# a320-polyvoks-vcf.net
KiCad netlist of a schematic drawn in EAGLE
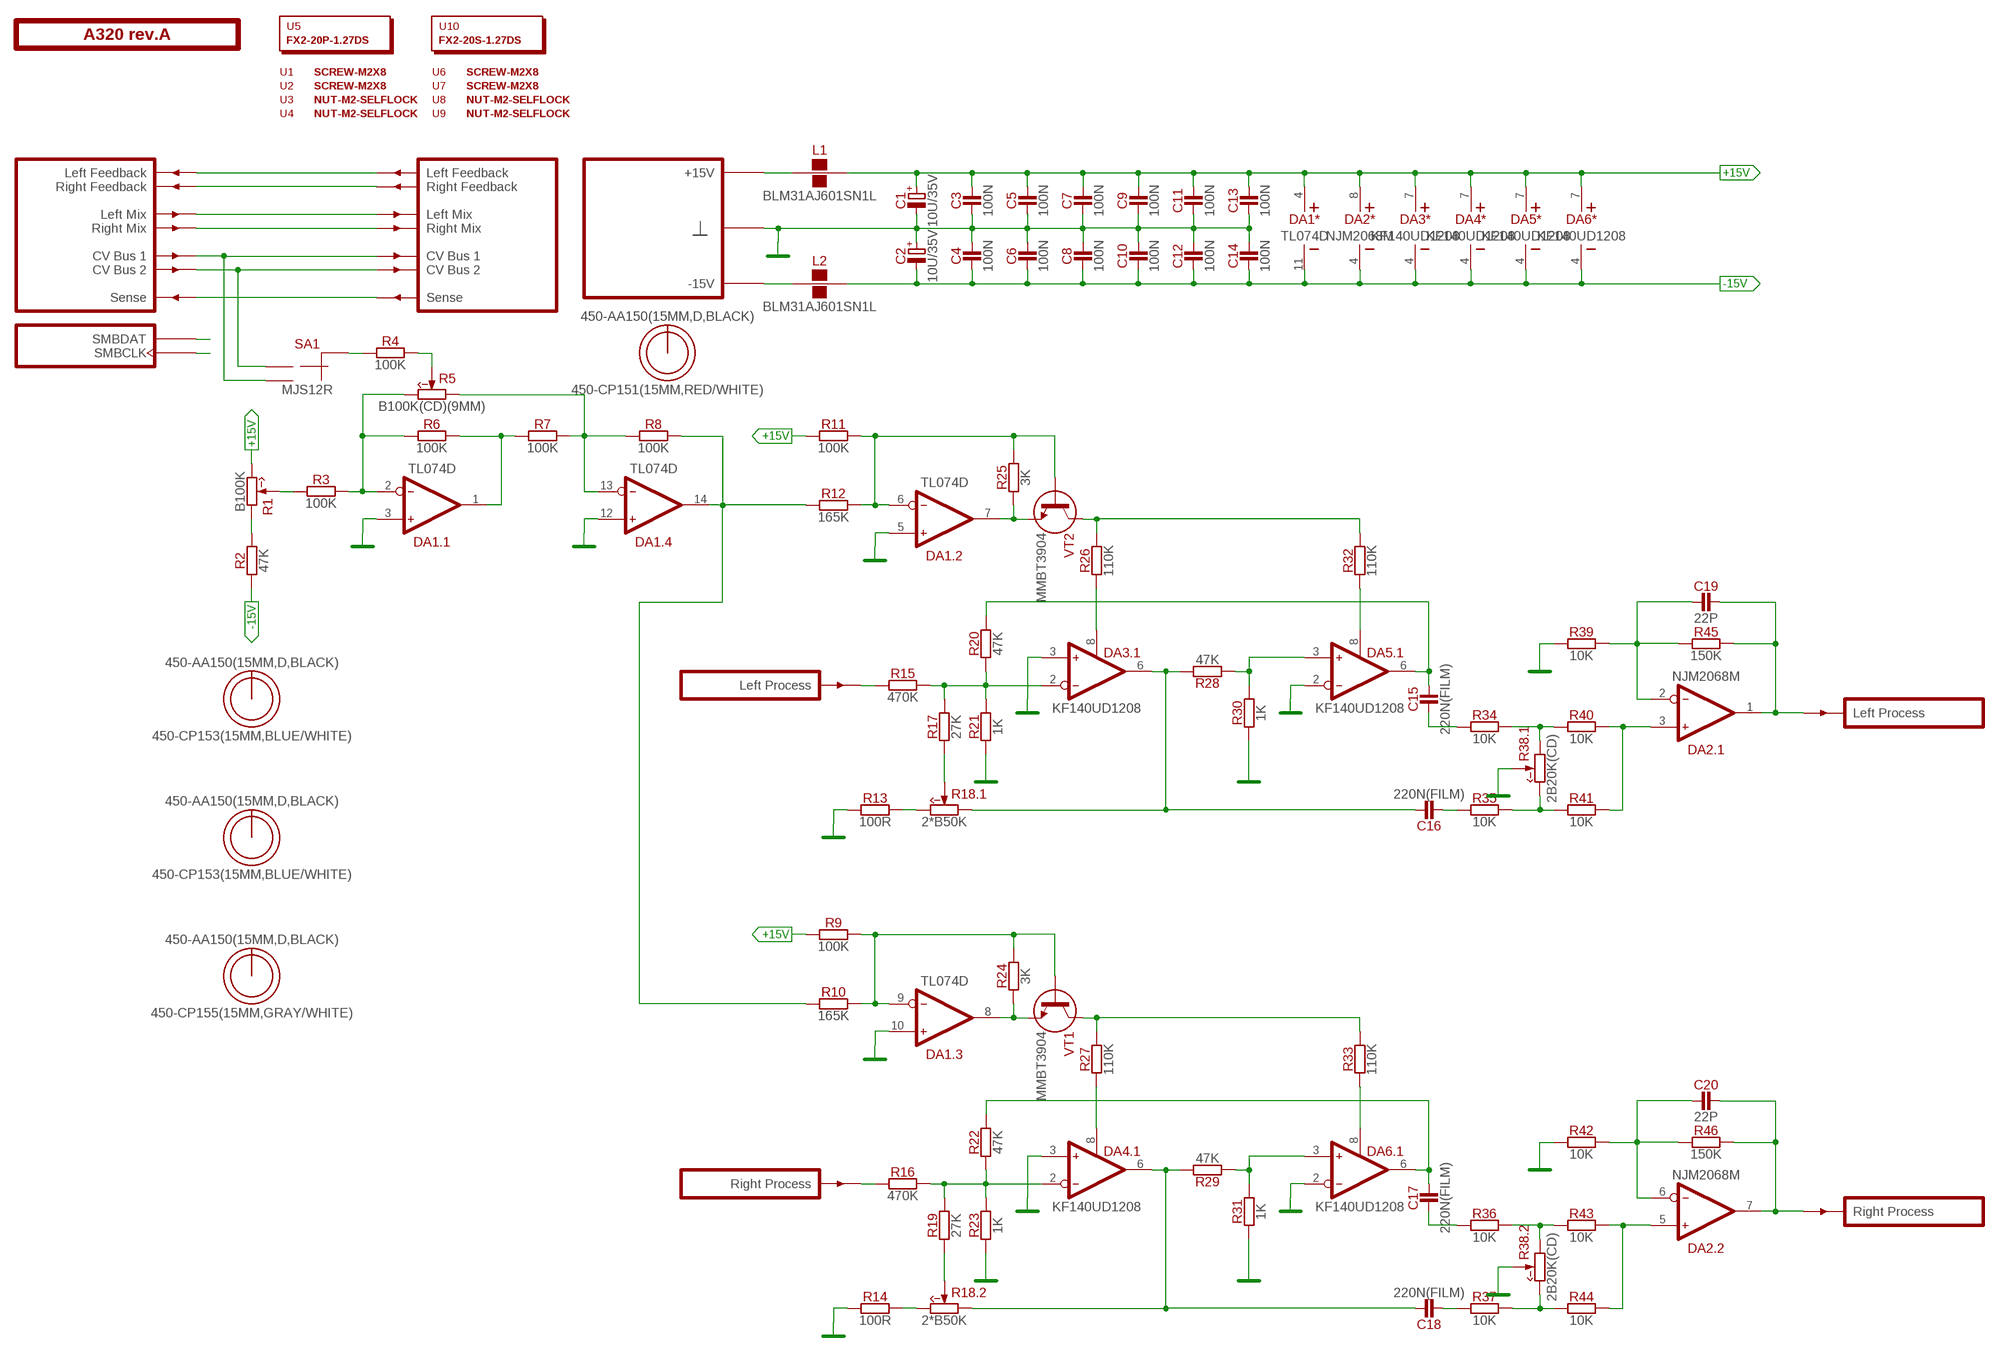
[diagram p0: schematic, sheet 1]

(export (version "E")
  (design (tool "Eeschema 10.0.6"))
  (components
    (comp (ref "C1")
      (value "10U/35V")
      (footprint "eagle-import:E2-5")
      (libsource (lib "eagle-import") (part "?10U/35V"))
    )
    (comp (ref "C2")
      (value "10U/35V")
      (footprint "eagle-import:E2-5")
      (libsource (lib "eagle-import") (part "?10U/35V"))
    )
    (comp (ref "C3")
      (value "100N")
      (footprint "eagle-import:C-0805")
      (libsource (lib "eagle-import") (part "?100N"))
    )
    (comp (ref "C4")
      (value "100N")
      (footprint "eagle-import:C-0805")
      (libsource (lib "eagle-import") (part "?100N"))
    )
    (comp (ref "C5")
      (value "100N")
      (footprint "eagle-import:C-0805")
      (libsource (lib "eagle-import") (part "?100N"))
    )
    (comp (ref "C6")
      (value "100N")
      (footprint "eagle-import:C-0805")
      (libsource (lib "eagle-import") (part "?100N"))
    )
    (comp (ref "C7")
      (value "100N")
      (footprint "eagle-import:C-0805")
      (libsource (lib "eagle-import") (part "?100N"))
    )
    (comp (ref "C8")
      (value "100N")
      (footprint "eagle-import:C-0805")
      (libsource (lib "eagle-import") (part "?100N"))
    )
    (comp (ref "C9")
      (value "100N")
      (footprint "eagle-import:C-0805")
      (libsource (lib "eagle-import") (part "?100N"))
    )
    (comp (ref "C10")
      (value "100N")
      (footprint "eagle-import:C-0805")
      (libsource (lib "eagle-import") (part "?100N"))
    )
    (comp (ref "C11")
      (value "100N")
      (footprint "eagle-import:C-0805")
      (libsource (lib "eagle-import") (part "?100N"))
    )
    (comp (ref "C12")
      (value "100N")
      (footprint "eagle-import:C-0805")
      (libsource (lib "eagle-import") (part "?100N"))
    )
    (comp (ref "C13")
      (value "100N")
      (footprint "eagle-import:C-0805")
      (libsource (lib "eagle-import") (part "?100N"))
    )
    (comp (ref "C14")
      (value "100N")
      (footprint "eagle-import:C-0805")
      (libsource (lib "eagle-import") (part "?100N"))
    )
    (comp (ref "C15")
      (value "220N(FILM)")
      (footprint "eagle-import:C050-025X075")
      (libsource (lib "eagle-import") (part "?220N(FILM)"))
    )
    (comp (ref "C16")
      (value "220N(FILM)")
      (footprint "eagle-import:C050-025X075")
      (libsource (lib "eagle-import") (part "?220N(FILM)"))
    )
    (comp (ref "C17")
      (value "220N(FILM)")
      (footprint "eagle-import:C050-025X075")
      (libsource (lib "eagle-import") (part "?220N(FILM)"))
    )
    (comp (ref "C18")
      (value "220N(FILM)")
      (footprint "eagle-import:C050-025X075")
      (libsource (lib "eagle-import") (part "?220N(FILM)"))
    )
    (comp (ref "C19")
      (value "22P")
      (footprint "eagle-import:C-0805")
      (libsource (lib "eagle-import") (part "?22P"))
    )
    (comp (ref "C20")
      (value "22P")
      (footprint "eagle-import:C-0805")
      (libsource (lib "eagle-import") (part "?22P"))
    )
    (comp (ref "DA1")
      (value "TL074D")
      (footprint "eagle-import:SO-14")
      (libsource (lib "eagle-import") (part "TL074D"))
    )
    (comp (ref "DA2")
      (value "NJM2068M")
      (footprint "eagle-import:SO-8")
      (libsource (lib "eagle-import") (part "NJM2068M"))
    )
    (comp (ref "DA3")
      (value "KF140UD1208")
      (footprint "eagle-import:SO-8")
      (libsource (lib "eagle-import") (part "KF140UD1208"))
    )
    (comp (ref "DA4")
      (value "KF140UD1208")
      (footprint "eagle-import:SO-8")
      (libsource (lib "eagle-import") (part "KF140UD1208"))
    )
    (comp (ref "DA5")
      (value "KF140UD1208")
      (footprint "eagle-import:SO-8")
      (libsource (lib "eagle-import") (part "KF140UD1208"))
    )
    (comp (ref "DA6")
      (value "KF140UD1208")
      (footprint "eagle-import:SO-8")
      (libsource (lib "eagle-import") (part "KF140UD1208"))
    )
    (comp (ref "L1")
      (value "BLM31AJ601SN1L")
      (footprint "eagle-import:1206")
      (libsource (lib "eagle-import") (part "BLM31AJ601SN1L"))
    )
    (comp (ref "L2")
      (value "BLM31AJ601SN1L")
      (footprint "eagle-import:1206")
      (libsource (lib "eagle-import") (part "BLM31AJ601SN1L"))
    )
    (comp (ref "O1")
      (value "450-AA150(15MM,D,BLACK)")
      (footprint "eagle-import:EMPTY")
      (libsource (lib "eagle-import") (part "450-AA?150(15MM,D,BLACK)"))
    )
    (comp (ref "O2")
      (value "450-CP153(15MM,BLUE/WHITE)")
      (footprint "eagle-import:EMPTY")
      (libsource (lib "eagle-import") (part "450-C?P153(15MM,BLUE/WHITE)"))
    )
    (comp (ref "O3")
      (value "450-AA150(15MM,D,BLACK)")
      (footprint "eagle-import:EMPTY")
      (libsource (lib "eagle-import") (part "450-AA?150(15MM,D,BLACK)"))
    )
    (comp (ref "O4")
      (value "450-CP153(15MM,BLUE/WHITE)")
      (footprint "eagle-import:EMPTY")
      (libsource (lib "eagle-import") (part "450-C?P153(15MM,BLUE/WHITE)"))
    )
    (comp (ref "O5")
      (value "450-AA150(15MM,D,BLACK)")
      (footprint "eagle-import:EMPTY")
      (libsource (lib "eagle-import") (part "450-AA?150(15MM,D,BLACK)"))
    )
    (comp (ref "O6")
      (value "450-CP155(15MM,GRAY/WHITE)")
      (footprint "eagle-import:EMPTY")
      (libsource (lib "eagle-import") (part "450-C?P155(15MM,GRAY/WHITE)"))
    )
    (comp (ref "O7")
      (value "450-AA150(15MM,D,BLACK)")
      (footprint "eagle-import:EMPTY")
      (libsource (lib "eagle-import") (part "450-AA?150(15MM,D,BLACK)"))
    )
    (comp (ref "O8")
      (value "450-CP151(15MM,RED/WHITE)")
      (footprint "eagle-import:EMPTY")
      (libsource (lib "eagle-import") (part "450-C?P151(15MM,RED/WHITE)"))
    )
    (comp (ref "PCB1")
      (value "A320 rev.A")
      (footprint "eagle-import:ST2-BOARD-50")
      (libsource (lib "eagle-import") (part "ST2-BOARD-?50"))
    )
    (comp (ref "R1")
      (value "B100K")
      (footprint "eagle-import:RV11-SINGLE")
      (libsource (lib "eagle-import") (part "?B100K"))
    )
    (comp (ref "R2")
      (value "47K")
      (footprint "eagle-import:R-0805")
      (libsource (lib "eagle-import") (part "?47K"))
    )
    (comp (ref "R3")
      (value "100K")
      (footprint "eagle-import:R-0805")
      (libsource (lib "eagle-import") (part "?100K"))
    )
    (comp (ref "R4")
      (value "100K")
      (footprint "eagle-import:R-0805")
      (libsource (lib "eagle-import") (part "?100K"))
    )
    (comp (ref "R5")
      (value "B100K(CD)(9MM)")
      (footprint "eagle-import:RV09-SINGLE")
      (libsource (lib "eagle-import") (part "?B100K(CD)(9MM)"))
    )
    (comp (ref "R6")
      (value "100K")
      (footprint "eagle-import:R-0805")
      (libsource (lib "eagle-import") (part "?100K"))
    )
    (comp (ref "R7")
      (value "100K")
      (footprint "eagle-import:R-0805")
      (libsource (lib "eagle-import") (part "?100K"))
    )
    (comp (ref "R8")
      (value "100K")
      (footprint "eagle-import:R-0805")
      (libsource (lib "eagle-import") (part "?100K"))
    )
    (comp (ref "R9")
      (value "100K")
      (footprint "eagle-import:R-0805")
      (libsource (lib "eagle-import") (part "?100K"))
    )
    (comp (ref "R10")
      (value "165K")
      (footprint "eagle-import:R-0805")
      (libsource (lib "eagle-import") (part "?165K"))
    )
    (comp (ref "R11")
      (value "100K")
      (footprint "eagle-import:R-0805")
      (libsource (lib "eagle-import") (part "?100K"))
    )
    (comp (ref "R12")
      (value "165K")
      (footprint "eagle-import:R-0805")
      (libsource (lib "eagle-import") (part "?165K"))
    )
    (comp (ref "R13")
      (value "100R")
      (footprint "eagle-import:R-0805")
      (libsource (lib "eagle-import") (part "?100R"))
    )
    (comp (ref "R14")
      (value "100R")
      (footprint "eagle-import:R-0805")
      (libsource (lib "eagle-import") (part "?100R"))
    )
    (comp (ref "R15")
      (value "470K")
      (footprint "eagle-import:R-0805")
      (libsource (lib "eagle-import") (part "?470K"))
    )
    (comp (ref "R16")
      (value "470K")
      (footprint "eagle-import:R-0805")
      (libsource (lib "eagle-import") (part "?470K"))
    )
    (comp (ref "R17")
      (value "27K")
      (footprint "eagle-import:R-0805")
      (libsource (lib "eagle-import") (part "?27K"))
    )
    (comp (ref "R18")
      (value "2*B50K")
      (footprint "eagle-import:RV11-DUAL")
      (libsource (lib "eagle-import") (part "potentiometers_2?B50K"))
    )
    (comp (ref "R19")
      (value "27K")
      (footprint "eagle-import:R-0805")
      (libsource (lib "eagle-import") (part "?27K"))
    )
    (comp (ref "R20")
      (value "47K")
      (footprint "eagle-import:R-0805")
      (libsource (lib "eagle-import") (part "?47K"))
    )
    (comp (ref "R21")
      (value "1K")
      (footprint "eagle-import:R-0805")
      (libsource (lib "eagle-import") (part "?1K"))
    )
    (comp (ref "R22")
      (value "47K")
      (footprint "eagle-import:R-0805")
      (libsource (lib "eagle-import") (part "?47K"))
    )
    (comp (ref "R23")
      (value "1K")
      (footprint "eagle-import:R-0805")
      (libsource (lib "eagle-import") (part "?1K"))
    )
    (comp (ref "R24")
      (value "3K")
      (footprint "eagle-import:R-0805")
      (libsource (lib "eagle-import") (part "?3K"))
    )
    (comp (ref "R25")
      (value "3K")
      (footprint "eagle-import:R-0805")
      (libsource (lib "eagle-import") (part "?3K"))
    )
    (comp (ref "R26")
      (value "110K")
      (footprint "eagle-import:R-0805")
      (libsource (lib "eagle-import") (part "?110K"))
    )
    (comp (ref "R27")
      (value "110K")
      (footprint "eagle-import:R-0805")
      (libsource (lib "eagle-import") (part "?110K"))
    )
    (comp (ref "R28")
      (value "47K")
      (footprint "eagle-import:R-0805")
      (libsource (lib "eagle-import") (part "?47K"))
    )
    (comp (ref "R29")
      (value "47K")
      (footprint "eagle-import:R-0805")
      (libsource (lib "eagle-import") (part "?47K"))
    )
    (comp (ref "R30")
      (value "1K")
      (footprint "eagle-import:R-0805")
      (libsource (lib "eagle-import") (part "?1K"))
    )
    (comp (ref "R31")
      (value "1K")
      (footprint "eagle-import:R-0805")
      (libsource (lib "eagle-import") (part "?1K"))
    )
    (comp (ref "R32")
      (value "110K")
      (footprint "eagle-import:R-0805")
      (libsource (lib "eagle-import") (part "?110K"))
    )
    (comp (ref "R33")
      (value "110K")
      (footprint "eagle-import:R-0805")
      (libsource (lib "eagle-import") (part "?110K"))
    )
    (comp (ref "R34")
      (value "10K")
      (footprint "eagle-import:R-0805")
      (libsource (lib "eagle-import") (part "?10K"))
    )
    (comp (ref "R35")
      (value "10K")
      (footprint "eagle-import:R-0805")
      (libsource (lib "eagle-import") (part "?10K"))
    )
    (comp (ref "R36")
      (value "10K")
      (footprint "eagle-import:R-0805")
      (libsource (lib "eagle-import") (part "?10K"))
    )
    (comp (ref "R37")
      (value "10K")
      (footprint "eagle-import:R-0805")
      (libsource (lib "eagle-import") (part "?10K"))
    )
    (comp (ref "R38")
      (value "2B20K(CD)")
      (footprint "eagle-import:RV11-DUAL")
      (libsource (lib "eagle-import") (part "2?B20K(CD)"))
    )
    (comp (ref "R39")
      (value "10K")
      (footprint "eagle-import:R-0805")
      (libsource (lib "eagle-import") (part "?10K"))
    )
    (comp (ref "R40")
      (value "10K")
      (footprint "eagle-import:R-0805")
      (libsource (lib "eagle-import") (part "?10K"))
    )
    (comp (ref "R41")
      (value "10K")
      (footprint "eagle-import:R-0805")
      (libsource (lib "eagle-import") (part "?10K"))
    )
    (comp (ref "R42")
      (value "10K")
      (footprint "eagle-import:R-0805")
      (libsource (lib "eagle-import") (part "?10K"))
    )
    (comp (ref "R43")
      (value "10K")
      (footprint "eagle-import:R-0805")
      (libsource (lib "eagle-import") (part "?10K"))
    )
    (comp (ref "R44")
      (value "10K")
      (footprint "eagle-import:R-0805")
      (libsource (lib "eagle-import") (part "?10K"))
    )
    (comp (ref "R45")
      (value "150K")
      (footprint "eagle-import:R-0805")
      (libsource (lib "eagle-import") (part "?150K"))
    )
    (comp (ref "R46")
      (value "150K")
      (footprint "eagle-import:R-0805")
      (libsource (lib "eagle-import") (part "?150K"))
    )
    (comp (ref "SA1")
      (value "MJS12R")
      (footprint "eagle-import:APEM-MJS12R")
      (libsource (lib "eagle-import") (part "MJS12R"))
    )
    (comp (ref "U1")
      (value "SCREW-M2X8")
      (footprint "eagle-import:EMPTY")
      (libsource (lib "eagle-import") (part "?SCREW-M2X8"))
    )
    (comp (ref "U2")
      (value "SCREW-M2X8")
      (footprint "eagle-import:EMPTY")
      (libsource (lib "eagle-import") (part "?SCREW-M2X8"))
    )
    (comp (ref "U3")
      (value "NUT-M2-SELFLOCK")
      (footprint "eagle-import:EMPTY")
      (libsource (lib "eagle-import") (part "?NUT-M2-SELFLOCK"))
    )
    (comp (ref "U4")
      (value "NUT-M2-SELFLOCK")
      (footprint "eagle-import:EMPTY")
      (libsource (lib "eagle-import") (part "?NUT-M2-SELFLOCK"))
    )
    (comp (ref "U5")
      (value "FX2-20P-1.27DS")
      (footprint "eagle-import:EMPTY")
      (libsource (lib "eagle-import") (part "?FX2-20P-1.27DS"))
    )
    (comp (ref "U6")
      (value "SCREW-M2X8")
      (footprint "eagle-import:EMPTY")
      (libsource (lib "eagle-import") (part "?SCREW-M2X8"))
    )
    (comp (ref "U7")
      (value "SCREW-M2X8")
      (footprint "eagle-import:EMPTY")
      (libsource (lib "eagle-import") (part "?SCREW-M2X8"))
    )
    (comp (ref "U8")
      (value "NUT-M2-SELFLOCK")
      (footprint "eagle-import:EMPTY")
      (libsource (lib "eagle-import") (part "?NUT-M2-SELFLOCK"))
    )
    (comp (ref "U9")
      (value "NUT-M2-SELFLOCK")
      (footprint "eagle-import:EMPTY")
      (libsource (lib "eagle-import") (part "?NUT-M2-SELFLOCK"))
    )
    (comp (ref "U10")
      (value "FX2-20S-1.27DS")
      (footprint "eagle-import:EMPTY")
      (libsource (lib "eagle-import") (part "?FX2-20S-1.27DS"))
    )
    (comp (ref "VT1")
      (value "MMBT3904")
      (footprint "eagle-import:SOT23")
      (libsource (lib "eagle-import") (part "?MMBT3904"))
    )
    (comp (ref "VT2")
      (value "MMBT3904")
      (footprint "eagle-import:SOT23")
      (libsource (lib "eagle-import") (part "?MMBT3904"))
    )
  )
  (nets
    (net (code "1") (name "+15V") (class "Default")
      (node (ref "C1") (pin "+") (pinfunction "+_+") (pintype "passive"))
      (node (ref "C11") (pin "2") (pinfunction "2_2") (pintype "passive"))
      (node (ref "C13") (pin "2") (pinfunction "2_2") (pintype "passive"))
      (node (ref "C3") (pin "2") (pinfunction "2_2") (pintype "passive"))
      (node (ref "C5") (pin "2") (pinfunction "2_2") (pintype "passive"))
      (node (ref "C7") (pin "2") (pinfunction "2_2") (pintype "passive"))
      (node (ref "C9") (pin "2") (pinfunction "2_2") (pintype "passive"))
      (node (ref "DA1") (pin "4") (pinfunction "V+_4") (pintype "power_in"))
      (node (ref "DA2") (pin "8") (pinfunction "V+_8") (pintype "power_in"))
      (node (ref "DA3") (pin "7") (pinfunction "V+_7") (pintype "power_in"))
      (node (ref "DA4") (pin "7") (pinfunction "V+_7") (pintype "power_in"))
      (node (ref "DA5") (pin "7") (pinfunction "V+_7") (pintype "power_in"))
      (node (ref "DA6") (pin "7") (pinfunction "V+_7") (pintype "power_in"))
      (node (ref "L1") (pin "2") (pinfunction "2_2") (pintype "passive"))
      (node (ref "R1") (pin "3") (pinfunction "CW_3") (pintype "passive"))
      (node (ref "R11") (pin "1") (pinfunction "1_1") (pintype "passive"))
      (node (ref "R9") (pin "1") (pinfunction "1_1") (pintype "passive"))
    )
    (net (code "2") (name "-15V") (class "Default")
      (node (ref "C10") (pin "1") (pinfunction "1_1") (pintype "passive"))
      (node (ref "C12") (pin "1") (pinfunction "1_1") (pintype "passive"))
      (node (ref "C14") (pin "1") (pinfunction "1_1") (pintype "passive"))
      (node (ref "C2") (pin "-") (pinfunction "-_-") (pintype "passive"))
      (node (ref "C4") (pin "1") (pinfunction "1_1") (pintype "passive"))
      (node (ref "C6") (pin "1") (pinfunction "1_1") (pintype "passive"))
      (node (ref "C8") (pin "1") (pinfunction "1_1") (pintype "passive"))
      (node (ref "DA1") (pin "11") (pinfunction "V-_11") (pintype "power_in"))
      (node (ref "DA2") (pin "4") (pinfunction "V-_4") (pintype "power_in"))
      (node (ref "DA3") (pin "4") (pinfunction "V-_4") (pintype "power_in"))
      (node (ref "DA4") (pin "4") (pinfunction "V-_4") (pintype "power_in"))
      (node (ref "DA5") (pin "4") (pinfunction "V-_4") (pintype "power_in"))
      (node (ref "DA6") (pin "4") (pinfunction "V-_4") (pintype "power_in"))
      (node (ref "L2") (pin "2") (pinfunction "2_2") (pintype "passive"))
      (node (ref "R2") (pin "1") (pinfunction "1_1") (pintype "passive"))
    )
    (net (code "3") (name "GND") (class "Default")
      (node (ref "C1") (pin "-") (pinfunction "-_-") (pintype "passive"))
      (node (ref "C10") (pin "2") (pinfunction "2_2") (pintype "passive"))
      (node (ref "C11") (pin "1") (pinfunction "1_1") (pintype "passive"))
      (node (ref "C12") (pin "2") (pinfunction "2_2") (pintype "passive"))
      (node (ref "C13") (pin "1") (pinfunction "1_1") (pintype "passive"))
      (node (ref "C14") (pin "2") (pinfunction "2_2") (pintype "passive"))
      (node (ref "C2") (pin "+") (pinfunction "+_+") (pintype "passive"))
      (node (ref "C3") (pin "1") (pinfunction "1_1") (pintype "passive"))
      (node (ref "C4") (pin "2") (pinfunction "2_2") (pintype "passive"))
      (node (ref "C5") (pin "1") (pinfunction "1_1") (pintype "passive"))
      (node (ref "C6") (pin "2") (pinfunction "2_2") (pintype "passive"))
      (node (ref "C7") (pin "1") (pinfunction "1_1") (pintype "passive"))
      (node (ref "C8") (pin "2") (pinfunction "2_2") (pintype "passive"))
      (node (ref "C9") (pin "1") (pinfunction "1_1") (pintype "passive"))
      (node (ref "DA1") (pin "10") (pinfunction "IN+_10") (pintype "input"))
      (node (ref "DA1") (pin "12") (pinfunction "IN+_12") (pintype "input"))
      (node (ref "DA1") (pin "3") (pinfunction "IN+_3") (pintype "input"))
      (node (ref "DA1") (pin "5") (pinfunction "IN+_5") (pintype "input"))
      (node (ref "DA3") (pin "3") (pinfunction "IN+_3") (pintype "input"))
      (node (ref "DA4") (pin "3") (pinfunction "IN+_3") (pintype "input"))
      (node (ref "DA5") (pin "2") (pinfunction "IN-_2") (pintype "input"))
      (node (ref "DA6") (pin "2") (pinfunction "IN-_2") (pintype "input"))
      (node (ref "PCB1") (pin "B4") (pinfunction "GND_B4") (pintype "bidirectional"))
      (node (ref "PCB1") (pin "B4'") (pinfunction "GND_B4'") (pintype "bidirectional"))
      (node (ref "PCB1") (pin "B5") (pinfunction "GND_B5") (pintype "bidirectional"))
      (node (ref "PCB1") (pin "B5'") (pinfunction "GND_B5'") (pintype "bidirectional"))
      (node (ref "PCB1") (pin "B6") (pinfunction "GND_B6") (pintype "bidirectional"))
      (node (ref "PCB1") (pin "B6'") (pinfunction "GND_B6'") (pintype "bidirectional"))
      (node (ref "PCB1") (pin "B7") (pinfunction "GND_B7") (pintype "bidirectional"))
      (node (ref "PCB1") (pin "B7'") (pinfunction "GND_B7'") (pintype "bidirectional"))
      (node (ref "PCB1") (pin "B8") (pinfunction "GND_B8") (pintype "bidirectional"))
      (node (ref "PCB1") (pin "B8'") (pinfunction "GND_B8'") (pintype "bidirectional"))
      (node (ref "R13") (pin "1") (pinfunction "1_1") (pintype "passive"))
      (node (ref "R14") (pin "1") (pinfunction "1_1") (pintype "passive"))
      (node (ref "R21") (pin "1") (pinfunction "1_1") (pintype "passive"))
      (node (ref "R23") (pin "1") (pinfunction "1_1") (pintype "passive"))
      (node (ref "R30") (pin "1") (pinfunction "1_1") (pintype "passive"))
      (node (ref "R31") (pin "1") (pinfunction "1_1") (pintype "passive"))
      (node (ref "R38") (pin "2") (pinfunction "W_2") (pintype "passive"))
      (node (ref "R38") (pin "2'") (pinfunction "W_2'") (pintype "passive"))
      (node (ref "R39") (pin "1") (pinfunction "1_1") (pintype "passive"))
      (node (ref "R42") (pin "1") (pinfunction "1_1") (pintype "passive"))
    )
    (net (code "4") (name "Net-(C15-Pad1)") (class "Default")
      (node (ref "C15") (pin "1") (pinfunction "1_1") (pintype "passive"))
      (node (ref "R34") (pin "1") (pinfunction "1_1") (pintype "passive"))
    )
    (net (code "5") (name "Net-(C16-Pad1)") (class "Default")
      (node (ref "C16") (pin "1") (pinfunction "1_1") (pintype "passive"))
      (node (ref "R35") (pin "1") (pinfunction "1_1") (pintype "passive"))
    )
    (net (code "6") (name "Net-(C17-Pad1)") (class "Default")
      (node (ref "C17") (pin "1") (pinfunction "1_1") (pintype "passive"))
      (node (ref "R36") (pin "1") (pinfunction "1_1") (pintype "passive"))
    )
    (net (code "7") (name "Net-(C18-Pad1)") (class "Default")
      (node (ref "C18") (pin "1") (pinfunction "1_1") (pintype "passive"))
      (node (ref "R37") (pin "1") (pinfunction "1_1") (pintype "passive"))
    )
    (net (code "8") (name "Net-(DA1B-IN-)") (class "Default")
      (node (ref "DA1") (pin "2") (pinfunction "IN-_2") (pintype "input"))
      (node (ref "R3") (pin "2") (pinfunction "2_2") (pintype "passive"))
      (node (ref "R5") (pin "3") (pinfunction "CW_3") (pintype "passive"))
      (node (ref "R6") (pin "1") (pinfunction "1_1") (pintype "passive"))
    )
    (net (code "9") (name "Net-(DA1B-OUT)") (class "Default")
      (node (ref "DA1") (pin "1") (pinfunction "OUT_1") (pintype "output"))
      (node (ref "R6") (pin "2") (pinfunction "2_2") (pintype "passive"))
      (node (ref "R7") (pin "1") (pinfunction "1_1") (pintype "passive"))
    )
    (net (code "10") (name "Net-(DA1C-IN-)") (class "Default")
      (node (ref "DA1") (pin "6") (pinfunction "IN-_6") (pintype "input"))
      (node (ref "R11") (pin "2") (pinfunction "2_2") (pintype "passive"))
      (node (ref "R12") (pin "2") (pinfunction "2_2") (pintype "passive"))
      (node (ref "R25") (pin "2") (pinfunction "2_2") (pintype "passive"))
      (node (ref "VT2") (pin "1") (pinfunction "B_1") (pintype "passive"))
    )
    (net (code "11") (name "Net-(DA1C-OUT)") (class "Default")
      (node (ref "DA1") (pin "7") (pinfunction "OUT_7") (pintype "output"))
      (node (ref "R25") (pin "1") (pinfunction "1_1") (pintype "passive"))
      (node (ref "VT2") (pin "2") (pinfunction "E_2") (pintype "passive"))
    )
    (net (code "12") (name "Net-(DA1D-IN-)") (class "Default")
      (node (ref "DA1") (pin "9") (pinfunction "IN-_9") (pintype "input"))
      (node (ref "R10") (pin "2") (pinfunction "2_2") (pintype "passive"))
      (node (ref "R24") (pin "2") (pinfunction "2_2") (pintype "passive"))
      (node (ref "R9") (pin "2") (pinfunction "2_2") (pintype "passive"))
      (node (ref "VT1") (pin "1") (pinfunction "B_1") (pintype "passive"))
    )
    (net (code "13") (name "Net-(DA1D-OUT)") (class "Default")
      (node (ref "DA1") (pin "8") (pinfunction "OUT_8") (pintype "output"))
      (node (ref "R24") (pin "1") (pinfunction "1_1") (pintype "passive"))
      (node (ref "VT1") (pin "2") (pinfunction "E_2") (pintype "passive"))
    )
    (net (code "14") (name "Net-(DA1E-IN-)") (class "Default")
      (node (ref "DA1") (pin "13") (pinfunction "IN-_13") (pintype "input"))
      (node (ref "R5") (pin "1") (pinfunction "CCW_1") (pintype "passive"))
      (node (ref "R7") (pin "2") (pinfunction "2_2") (pintype "passive"))
      (node (ref "R8") (pin "1") (pinfunction "1_1") (pintype "passive"))
    )
    (net (code "15") (name "Net-(DA1E-OUT)") (class "Default")
      (node (ref "DA1") (pin "14") (pinfunction "OUT_14") (pintype "output"))
      (node (ref "R10") (pin "1") (pinfunction "1_1") (pintype "passive"))
      (node (ref "R12") (pin "1") (pinfunction "1_1") (pintype "passive"))
      (node (ref "R8") (pin "2") (pinfunction "2_2") (pintype "passive"))
    )
    (net (code "16") (name "Net-(DA2B-IN+)") (class "Default")
      (node (ref "DA2") (pin "3") (pinfunction "IN+_3") (pintype "input"))
      (node (ref "R40") (pin "2") (pinfunction "2_2") (pintype "passive"))
      (node (ref "R41") (pin "2") (pinfunction "2_2") (pintype "passive"))
    )
    (net (code "17") (name "Net-(DA2B-IN-)") (class "Default")
      (node (ref "C19") (pin "1") (pinfunction "1_1") (pintype "passive"))
      (node (ref "DA2") (pin "2") (pinfunction "IN-_2") (pintype "input"))
      (node (ref "R39") (pin "2") (pinfunction "2_2") (pintype "passive"))
      (node (ref "R45") (pin "1") (pinfunction "1_1") (pintype "passive"))
    )
    (net (code "18") (name "Net-(DA2B-OUT)") (class "Default")
      (node (ref "C19") (pin "2") (pinfunction "2_2") (pintype "passive"))
      (node (ref "DA2") (pin "1") (pinfunction "OUT_1") (pintype "output"))
      (node (ref "PCB1") (pin "BOUTL'") (pinfunction "OUTL_BOUTL'") (pintype "bidirectional"))
      (node (ref "R45") (pin "2") (pinfunction "2_2") (pintype "passive"))
    )
    (net (code "19") (name "Net-(DA2C-IN+)") (class "Default")
      (node (ref "DA2") (pin "5") (pinfunction "IN+_5") (pintype "input"))
      (node (ref "R43") (pin "2") (pinfunction "2_2") (pintype "passive"))
      (node (ref "R44") (pin "2") (pinfunction "2_2") (pintype "passive"))
    )
    (net (code "20") (name "Net-(DA2C-IN-)") (class "Default")
      (node (ref "C20") (pin "1") (pinfunction "1_1") (pintype "passive"))
      (node (ref "DA2") (pin "6") (pinfunction "IN-_6") (pintype "input"))
      (node (ref "R42") (pin "2") (pinfunction "2_2") (pintype "passive"))
      (node (ref "R46") (pin "1") (pinfunction "1_1") (pintype "passive"))
    )
    (net (code "21") (name "Net-(DA2C-OUT)") (class "Default")
      (node (ref "C20") (pin "2") (pinfunction "2_2") (pintype "passive"))
      (node (ref "DA2") (pin "7") (pinfunction "OUT_7") (pintype "output"))
      (node (ref "PCB1") (pin "BOUTR'") (pinfunction "OUTR_BOUTR'") (pintype "bidirectional"))
      (node (ref "R46") (pin "2") (pinfunction "2_2") (pintype "passive"))
    )
    (net (code "22") (name "Net-(DA3B-IN-)") (class "Default")
      (node (ref "DA3") (pin "2") (pinfunction "IN-_2") (pintype "input"))
      (node (ref "R15") (pin "2") (pinfunction "2_2") (pintype "passive"))
      (node (ref "R17") (pin "2") (pinfunction "2_2") (pintype "passive"))
      (node (ref "R20") (pin "1") (pinfunction "1_1") (pintype "passive"))
      (node (ref "R21") (pin "2") (pinfunction "2_2") (pintype "passive"))
    )
    (net (code "23") (name "Net-(DA3B-ISET)") (class "Default")
      (node (ref "DA3") (pin "8") (pinfunction "ISET_8") (pintype "bidirectional"))
      (node (ref "R26") (pin "1") (pinfunction "1_1") (pintype "passive"))
    )
    (net (code "24") (name "Net-(DA3B-OUT)") (class "Default")
      (node (ref "C16") (pin "2") (pinfunction "2_2") (pintype "passive"))
      (node (ref "DA3") (pin "6") (pinfunction "OUT_6") (pintype "output"))
      (node (ref "R18") (pin "1") (pinfunction "CCW_1") (pintype "passive"))
      (node (ref "R28") (pin "2") (pinfunction "2_2") (pintype "passive"))
    )
    (net (code "25") (name "Net-(DA4B-IN-)") (class "Default")
      (node (ref "DA4") (pin "2") (pinfunction "IN-_2") (pintype "input"))
      (node (ref "R16") (pin "2") (pinfunction "2_2") (pintype "passive"))
      (node (ref "R19") (pin "2") (pinfunction "2_2") (pintype "passive"))
      (node (ref "R22") (pin "1") (pinfunction "1_1") (pintype "passive"))
      (node (ref "R23") (pin "2") (pinfunction "2_2") (pintype "passive"))
    )
    (net (code "26") (name "Net-(DA4B-ISET)") (class "Default")
      (node (ref "DA4") (pin "8") (pinfunction "ISET_8") (pintype "bidirectional"))
      (node (ref "R27") (pin "1") (pinfunction "1_1") (pintype "passive"))
    )
    (net (code "27") (name "Net-(DA4B-OUT)") (class "Default")
      (node (ref "C18") (pin "2") (pinfunction "2_2") (pintype "passive"))
      (node (ref "DA4") (pin "6") (pinfunction "OUT_6") (pintype "output"))
      (node (ref "R18") (pin "1'") (pinfunction "CCW_1'") (pintype "passive"))
      (node (ref "R29") (pin "2") (pinfunction "2_2") (pintype "passive"))
    )
    (net (code "28") (name "Net-(DA5B-IN+)") (class "Default")
      (node (ref "DA5") (pin "3") (pinfunction "IN+_3") (pintype "input"))
      (node (ref "R28") (pin "1") (pinfunction "1_1") (pintype "passive"))
      (node (ref "R30") (pin "2") (pinfunction "2_2") (pintype "passive"))
    )
    (net (code "29") (name "Net-(DA5B-ISET)") (class "Default")
      (node (ref "DA5") (pin "8") (pinfunction "ISET_8") (pintype "bidirectional"))
      (node (ref "R32") (pin "1") (pinfunction "1_1") (pintype "passive"))
    )
    (net (code "30") (name "Net-(DA5B-OUT)") (class "Default")
      (node (ref "C15") (pin "2") (pinfunction "2_2") (pintype "passive"))
      (node (ref "DA5") (pin "6") (pinfunction "OUT_6") (pintype "output"))
      (node (ref "R20") (pin "2") (pinfunction "2_2") (pintype "passive"))
    )
    (net (code "31") (name "Net-(DA6B-IN+)") (class "Default")
      (node (ref "DA6") (pin "3") (pinfunction "IN+_3") (pintype "input"))
      (node (ref "R29") (pin "1") (pinfunction "1_1") (pintype "passive"))
      (node (ref "R31") (pin "2") (pinfunction "2_2") (pintype "passive"))
    )
    (net (code "32") (name "Net-(DA6B-ISET)") (class "Default")
      (node (ref "DA6") (pin "8") (pinfunction "ISET_8") (pintype "bidirectional"))
      (node (ref "R33") (pin "1") (pinfunction "1_1") (pintype "passive"))
    )
    (net (code "33") (name "Net-(DA6B-OUT)") (class "Default")
      (node (ref "C17") (pin "2") (pinfunction "2_2") (pintype "passive"))
      (node (ref "DA6") (pin "6") (pinfunction "OUT_6") (pintype "output"))
      (node (ref "R22") (pin "2") (pinfunction "2_2") (pintype "passive"))
    )
    (net (code "34") (name "Net-(L1-Pad1)") (class "Default")
      (node (ref "L1") (pin "1") (pinfunction "1_1") (pintype "passive"))
      (node (ref "PCB1") (pin "A+15") (pinfunction "P+15V_A+15") (pintype "bidirectional"))
      (node (ref "PCB1") (pin "A+15'") (pinfunction "P+15V_A+15'") (pintype "bidirectional"))
      (node (ref "PCB1") (pin "B+15") (pinfunction "P+15V_B+15") (pintype "bidirectional"))
      (node (ref "PCB1") (pin "B+15'") (pinfunction "P+15V_B+15'") (pintype "bidirectional"))
    )
    (net (code "35") (name "Net-(L2-Pad1)") (class "Default")
      (node (ref "L2") (pin "1") (pinfunction "1_1") (pintype "passive"))
      (node (ref "PCB1") (pin "A-15") (pinfunction "P-15V_A-15") (pintype "bidirectional"))
      (node (ref "PCB1") (pin "A-15'") (pinfunction "P-15V_A-15'") (pintype "bidirectional"))
      (node (ref "PCB1") (pin "B-15") (pinfunction "P-15V_B-15") (pintype "bidirectional"))
      (node (ref "PCB1") (pin "B-15'") (pinfunction "P-15V_B-15'") (pintype "bidirectional"))
    )
    (net (code "36") (name "Net-(PCB1B-INL)") (class "Default")
      (node (ref "PCB1") (pin "BINL") (pinfunction "INL_BINL") (pintype "bidirectional"))
      (node (ref "R15") (pin "1") (pinfunction "1_1") (pintype "passive"))
    )
    (net (code "37") (name "Net-(PCB1C-INR)") (class "Default")
      (node (ref "PCB1") (pin "BINR") (pinfunction "INR_BINR") (pintype "bidirectional"))
      (node (ref "R16") (pin "1") (pinfunction "1_1") (pintype "passive"))
    )
    (net (code "38") (name "Net-(PCB1F-CV1)") (class "Default")
      (node (ref "PCB1") (pin "ACV1") (pinfunction "CV1_ACV1") (pintype "bidirectional"))
      (node (ref "PCB1") (pin "ACV1'") (pinfunction "CV1'_ACV1'") (pintype "bidirectional"))
      (node (ref "SA1") (pin "NO") (pinfunction "2_NO") (pintype "passive"))
    )
    (net (code "39") (name "Net-(PCB1F-CV2)") (class "Default")
      (node (ref "PCB1") (pin "ACV2") (pinfunction "CV2_ACV2") (pintype "bidirectional"))
      (node (ref "PCB1") (pin "ACV2'") (pinfunction "CV2'_ACV2'") (pintype "bidirectional"))
      (node (ref "SA1") (pin "NC") (pinfunction "1_NC") (pintype "passive"))
    )
    (net (code "40") (name "Net-(PCB1F-LFBK)") (class "Default")
      (node (ref "PCB1") (pin "ALFBK") (pinfunction "LFBK_ALFBK") (pintype "bidirectional"))
      (node (ref "PCB1") (pin "ALFBK'") (pinfunction "LFBK'_ALFBK'") (pintype "bidirectional"))
    )
    (net (code "41") (name "Net-(PCB1F-LMIX)") (class "Default")
      (node (ref "PCB1") (pin "ALMIX") (pinfunction "LMIX_ALMIX") (pintype "bidirectional"))
      (node (ref "PCB1") (pin "ALMIX'") (pinfunction "LMIX'_ALMIX'") (pintype "bidirectional"))
    )
    (net (code "42") (name "Net-(PCB1F-RFBK)") (class "Default")
      (node (ref "PCB1") (pin "ARFBK") (pinfunction "RFBK_ARFBK") (pintype "bidirectional"))
      (node (ref "PCB1") (pin "ARFBK'") (pinfunction "RFBK'_ARFBK'") (pintype "bidirectional"))
    )
    (net (code "43") (name "Net-(PCB1F-RMIX)") (class "Default")
      (node (ref "PCB1") (pin "ARMIX") (pinfunction "RMIX_ARMIX") (pintype "bidirectional"))
      (node (ref "PCB1") (pin "ARMIX'") (pinfunction "RMIX'_ARMIX'") (pintype "bidirectional"))
    )
    (net (code "44") (name "Net-(PCB1F-SENSE)") (class "Default")
      (node (ref "PCB1") (pin "BSENSE") (pinfunction "SENSE_BSENSE") (pintype "bidirectional"))
      (node (ref "PCB1") (pin "BSENSE'") (pinfunction "SENSE'_BSENSE'") (pintype "bidirectional"))
    )
    (net (code "45") (name "Net-(PCB1H-SMBCLK-PadASMBCLK')") (class "Default")
      (node (ref "PCB1") (pin "ASMBCLK") (pinfunction "SMBCLK_ASMBCLK") (pintype "bidirectional"))
      (node (ref "PCB1") (pin "ASMBCLK'") (pinfunction "SMBCLK_ASMBCLK'") (pintype "bidirectional"))
    )
    (net (code "46") (name "Net-(PCB1H-SMBDAT-PadASMBDAT')") (class "Default")
      (node (ref "PCB1") (pin "ASMBDAT") (pinfunction "SMBDAT_ASMBDAT") (pintype "bidirectional"))
      (node (ref "PCB1") (pin "ASMBDAT'") (pinfunction "SMBDAT_ASMBDAT'") (pintype "bidirectional"))
    )
    (net (code "47") (name "Net-(R1-CCW)") (class "Default")
      (node (ref "R1") (pin "1") (pinfunction "CCW_1") (pintype "passive"))
      (node (ref "R2") (pin "2") (pinfunction "2_2") (pintype "passive"))
    )
    (net (code "48") (name "Net-(R1-W)") (class "Default")
      (node (ref "R1") (pin "2") (pinfunction "W_2") (pintype "passive"))
      (node (ref "R3") (pin "1") (pinfunction "1_1") (pintype "passive"))
    )
    (net (code "49") (name "Net-(R5-W)") (class "Default")
      (node (ref "R4") (pin "2") (pinfunction "2_2") (pintype "passive"))
      (node (ref "R5") (pin "2") (pinfunction "W_2") (pintype "passive"))
    )
    (net (code "50") (name "Net-(R18A-CW)") (class "Default")
      (node (ref "R13") (pin "2") (pinfunction "2_2") (pintype "passive"))
      (node (ref "R18") (pin "3") (pinfunction "CW_3") (pintype "passive"))
    )
    (net (code "51") (name "Net-(R18A-W)") (class "Default")
      (node (ref "R17") (pin "1") (pinfunction "1_1") (pintype "passive"))
      (node (ref "R18") (pin "2") (pinfunction "W_2") (pintype "passive"))
    )
    (net (code "52") (name "Net-(R18B-CW)") (class "Default")
      (node (ref "R14") (pin "2") (pinfunction "2_2") (pintype "passive"))
      (node (ref "R18") (pin "3'") (pinfunction "CW_3'") (pintype "passive"))
    )
    (net (code "53") (name "Net-(R18B-W)") (class "Default")
      (node (ref "R18") (pin "2'") (pinfunction "W_2'") (pintype "passive"))
      (node (ref "R19") (pin "1") (pinfunction "1_1") (pintype "passive"))
    )
    (net (code "54") (name "Net-(R38A-CCW)") (class "Default")
      (node (ref "R34") (pin "2") (pinfunction "2_2") (pintype "passive"))
      (node (ref "R38") (pin "1") (pinfunction "CCW_1") (pintype "passive"))
      (node (ref "R40") (pin "1") (pinfunction "1_1") (pintype "passive"))
    )
    (net (code "55") (name "Net-(R38A-CW)") (class "Default")
      (node (ref "R35") (pin "2") (pinfunction "2_2") (pintype "passive"))
      (node (ref "R38") (pin "3") (pinfunction "CW_3") (pintype "passive"))
      (node (ref "R41") (pin "1") (pinfunction "1_1") (pintype "passive"))
    )
    (net (code "56") (name "Net-(R38B-CCW)") (class "Default")
      (node (ref "R36") (pin "2") (pinfunction "2_2") (pintype "passive"))
      (node (ref "R38") (pin "1'") (pinfunction "CCW_1'") (pintype "passive"))
      (node (ref "R43") (pin "1") (pinfunction "1_1") (pintype "passive"))
    )
    (net (code "57") (name "Net-(R38B-CW)") (class "Default")
      (node (ref "R37") (pin "2") (pinfunction "2_2") (pintype "passive"))
      (node (ref "R38") (pin "3'") (pinfunction "CW_3'") (pintype "passive"))
      (node (ref "R44") (pin "1") (pinfunction "1_1") (pintype "passive"))
    )
    (net (code "58") (name "Net-(SA1-CM)") (class "Default")
      (node (ref "R4") (pin "1") (pinfunction "1_1") (pintype "passive"))
      (node (ref "SA1") (pin "C") (pinfunction "CM_C") (pintype "passive"))
    )
    (net (code "59") (name "Net-(VT1-C)") (class "Default")
      (node (ref "R27") (pin "2") (pinfunction "2_2") (pintype "passive"))
      (node (ref "R33") (pin "2") (pinfunction "2_2") (pintype "passive"))
      (node (ref "VT1") (pin "3") (pinfunction "C_3") (pintype "passive"))
    )
    (net (code "60") (name "Net-(VT2-C)") (class "Default")
      (node (ref "R26") (pin "2") (pinfunction "2_2") (pintype "passive"))
      (node (ref "R32") (pin "2") (pinfunction "2_2") (pintype "passive"))
      (node (ref "VT2") (pin "3") (pinfunction "C_3") (pintype "passive"))
    )
  )
)
